# ADC_schematic.net
KiCad netlist of a schematic drawn in Altium Designer
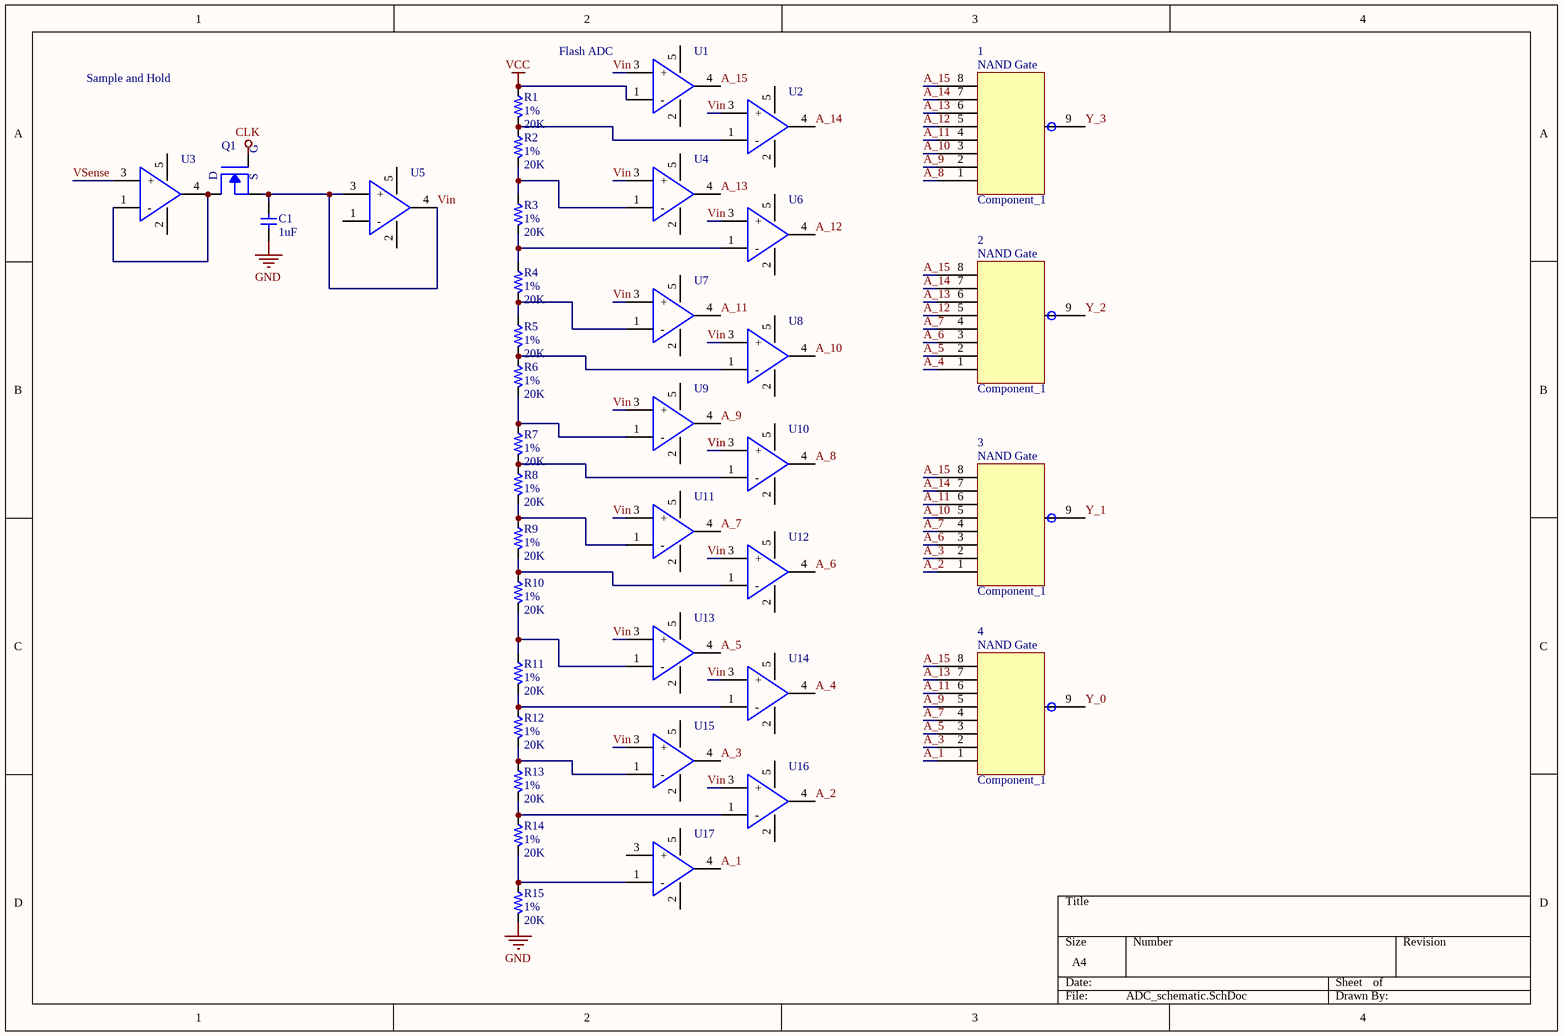
[diagram p0: ADC_schematic.SchDoc]

(export (version "E")
  (design (tool "Eeschema 10.0.6"))
  (components
    (comp (ref "1") (value "Component_1") (libsource (lib "8_in_NAND") (part "Component_1")))
    (comp (ref "2") (value "Component_1") (libsource (lib "8_in_NAND") (part "Component_1")))
    (comp (ref "3") (value "Component_1") (libsource (lib "8_in_NAND") (part "Component_1")))
    (comp (ref "4") (value "Component_1") (libsource (lib "8_in_NAND") (part "Component_1")))
    (comp (ref "C1")
      (value "1uF")
      (footprint "PCB_GENERIC_SMD_0603")
      (description "CAP CER 0603 1uF 16V X5R 20%")
      (fields (field (name "TOLERANCE") "20%") (field (name "VOLTAGE") "16V"))
      (libsource (lib "CAP") (part "C060-0001U-00"))
    )
    (comp (ref "Q1")
      (value "NMOS - SSM3K333R")
      (footprint "NMOS - SSM3K333R - SOTFL95P180X88-3M")
      (description "MOSFET N CH 30V 6A 2-3Z1A")
      (libsource (lib "NMOS") (part "NMOS - SSM3K333R"))
    )
    (comp (ref "R1")
      (value "20K")
      (footprint "PCB_GENERIC_SMD_0603")
      (description "RES 0603 10K 1% 100mW")
      (fields
        (field (name "POWER") "100mW")
        (field (name "TOLERANCE") "1%")
        (field (name "Comment") "R060-00103-01")
      )
      (libsource (lib "RES") (part "R060-00103-01"))
    )
    (comp (ref "R2")
      (value "20K")
      (footprint "PCB_GENERIC_SMD_0603")
      (description "RES 0603 10K 1% 100mW")
      (fields
        (field (name "POWER") "100mW")
        (field (name "TOLERANCE") "1%")
        (field (name "Comment") "R060-00103-01")
      )
      (libsource (lib "RES") (part "R060-00103-01"))
    )
    (comp (ref "R3")
      (value "20K")
      (footprint "PCB_GENERIC_SMD_0603")
      (description "RES 0603 10K 1% 100mW")
      (fields
        (field (name "POWER") "100mW")
        (field (name "TOLERANCE") "1%")
        (field (name "Comment") "R060-00103-01")
      )
      (libsource (lib "RES") (part "R060-00103-01"))
    )
    (comp (ref "R4")
      (value "20K")
      (footprint "PCB_GENERIC_SMD_0603")
      (description "RES 0603 10K 1% 100mW")
      (fields
        (field (name "POWER") "100mW")
        (field (name "TOLERANCE") "1%")
        (field (name "Comment") "R060-00103-01")
      )
      (libsource (lib "RES") (part "R060-00103-01"))
    )
    (comp (ref "R5")
      (value "20K")
      (footprint "PCB_GENERIC_SMD_0603")
      (description "RES 0603 10K 1% 100mW")
      (fields
        (field (name "POWER") "100mW")
        (field (name "TOLERANCE") "1%")
        (field (name "Comment") "R060-00103-01")
      )
      (libsource (lib "RES") (part "R060-00103-01"))
    )
    (comp (ref "R6")
      (value "20K")
      (footprint "PCB_GENERIC_SMD_0603")
      (description "RES 0603 10K 1% 100mW")
      (fields
        (field (name "POWER") "100mW")
        (field (name "TOLERANCE") "1%")
        (field (name "Comment") "R060-00103-01")
      )
      (libsource (lib "RES") (part "R060-00103-01"))
    )
    (comp (ref "R7")
      (value "20K")
      (footprint "PCB_GENERIC_SMD_0603")
      (description "RES 0603 10K 1% 100mW")
      (fields
        (field (name "POWER") "100mW")
        (field (name "TOLERANCE") "1%")
        (field (name "Comment") "R060-00103-01")
      )
      (libsource (lib "RES") (part "R060-00103-01"))
    )
    (comp (ref "R8")
      (value "20K")
      (footprint "PCB_GENERIC_SMD_0603")
      (description "RES 0603 10K 1% 100mW")
      (fields
        (field (name "POWER") "100mW")
        (field (name "TOLERANCE") "1%")
        (field (name "Comment") "R060-00103-01")
      )
      (libsource (lib "RES") (part "R060-00103-01"))
    )
    (comp (ref "R9")
      (value "20K")
      (footprint "PCB_GENERIC_SMD_0603")
      (description "RES 0603 10K 1% 100mW")
      (fields
        (field (name "POWER") "100mW")
        (field (name "TOLERANCE") "1%")
        (field (name "Comment") "R060-00103-01")
      )
      (libsource (lib "RES") (part "R060-00103-01"))
    )
    (comp (ref "R10")
      (value "20K")
      (footprint "PCB_GENERIC_SMD_0603")
      (description "RES 0603 10K 1% 100mW")
      (fields
        (field (name "POWER") "100mW")
        (field (name "TOLERANCE") "1%")
        (field (name "Comment") "R060-00103-01")
      )
      (libsource (lib "RES") (part "R060-00103-01"))
    )
    (comp (ref "R11")
      (value "20K")
      (footprint "PCB_GENERIC_SMD_0603")
      (description "RES 0603 10K 1% 100mW")
      (fields
        (field (name "POWER") "100mW")
        (field (name "TOLERANCE") "1%")
        (field (name "Comment") "R060-00103-01")
      )
      (libsource (lib "RES") (part "R060-00103-01"))
    )
    (comp (ref "R12")
      (value "20K")
      (footprint "PCB_GENERIC_SMD_0603")
      (description "RES 0603 10K 1% 100mW")
      (fields
        (field (name "POWER") "100mW")
        (field (name "TOLERANCE") "1%")
        (field (name "Comment") "R060-00103-01")
      )
      (libsource (lib "RES") (part "R060-00103-01"))
    )
    (comp (ref "R13")
      (value "20K")
      (footprint "PCB_GENERIC_SMD_0603")
      (description "RES 0603 10K 1% 100mW")
      (fields
        (field (name "POWER") "100mW")
        (field (name "TOLERANCE") "1%")
        (field (name "Comment") "R060-00103-01")
      )
      (libsource (lib "RES") (part "R060-00103-01"))
    )
    (comp (ref "R14")
      (value "20K")
      (footprint "PCB_GENERIC_SMD_0603")
      (description "RES 0603 10K 1% 100mW")
      (fields
        (field (name "POWER") "100mW")
        (field (name "TOLERANCE") "1%")
        (field (name "Comment") "R060-00103-01")
      )
      (libsource (lib "RES") (part "R060-00103-01"))
    )
    (comp (ref "R15")
      (value "20K")
      (footprint "PCB_GENERIC_SMD_0603")
      (description "RES 0603 10K 1% 100mW")
      (fields
        (field (name "POWER") "100mW")
        (field (name "TOLERANCE") "1%")
        (field (name "Comment") "R060-00103-01")
      )
      (libsource (lib "RES") (part "R060-00103-01"))
    )
    (comp (ref "U1")
      (value "AP331A")
      (footprint "SOT95P285X130-5N")
      (description "Single Channel Comparator, Open Drain, SC-74A/SOT-753")
      (libsource (lib "Op_Amp") (part "AP331A"))
    )
    (comp (ref "U2")
      (value "AP331A")
      (footprint "SOT95P285X130-5N")
      (description "Single Channel Comparator, Open Drain, SC-74A/SOT-753")
      (libsource (lib "Op_Amp") (part "AP331A"))
    )
    (comp (ref "U3")
      (value "AP331A")
      (footprint "SOT95P285X130-5N")
      (description "Single Channel Comparator, Open Drain, SC-74A/SOT-753")
      (libsource (lib "Op_Amp") (part "AP331A"))
    )
    (comp (ref "U4")
      (value "AP331A")
      (footprint "SOT95P285X130-5N")
      (description "Single Channel Comparator, Open Drain, SC-74A/SOT-753")
      (libsource (lib "Op_Amp") (part "AP331A"))
    )
    (comp (ref "U5")
      (value "AP331A")
      (footprint "SOT95P285X130-5N")
      (description "Single Channel Comparator, Open Drain, SC-74A/SOT-753")
      (libsource (lib "Op_Amp") (part "AP331A"))
    )
    (comp (ref "U6")
      (value "AP331A")
      (footprint "SOT95P285X130-5N")
      (description "Single Channel Comparator, Open Drain, SC-74A/SOT-753")
      (libsource (lib "Op_Amp") (part "AP331A"))
    )
    (comp (ref "U7")
      (value "AP331A")
      (footprint "SOT95P285X130-5N")
      (description "Single Channel Comparator, Open Drain, SC-74A/SOT-753")
      (libsource (lib "Op_Amp") (part "AP331A"))
    )
    (comp (ref "U8")
      (value "AP331A")
      (footprint "SOT95P285X130-5N")
      (description "Single Channel Comparator, Open Drain, SC-74A/SOT-753")
      (libsource (lib "Op_Amp") (part "AP331A"))
    )
    (comp (ref "U9")
      (value "AP331A")
      (footprint "SOT95P285X130-5N")
      (description "Single Channel Comparator, Open Drain, SC-74A/SOT-753")
      (libsource (lib "Op_Amp") (part "AP331A"))
    )
    (comp (ref "U10")
      (value "AP331A")
      (footprint "SOT95P285X130-5N")
      (description "Single Channel Comparator, Open Drain, SC-74A/SOT-753")
      (libsource (lib "Op_Amp") (part "AP331A"))
    )
    (comp (ref "U11")
      (value "AP331A")
      (footprint "SOT95P285X130-5N")
      (description "Single Channel Comparator, Open Drain, SC-74A/SOT-753")
      (libsource (lib "Op_Amp") (part "AP331A"))
    )
    (comp (ref "U12")
      (value "AP331A")
      (footprint "SOT95P285X130-5N")
      (description "Single Channel Comparator, Open Drain, SC-74A/SOT-753")
      (libsource (lib "Op_Amp") (part "AP331A"))
    )
    (comp (ref "U13")
      (value "AP331A")
      (footprint "SOT95P285X130-5N")
      (description "Single Channel Comparator, Open Drain, SC-74A/SOT-753")
      (libsource (lib "Op_Amp") (part "AP331A"))
    )
    (comp (ref "U14")
      (value "AP331A")
      (footprint "SOT95P285X130-5N")
      (description "Single Channel Comparator, Open Drain, SC-74A/SOT-753")
      (libsource (lib "Op_Amp") (part "AP331A"))
    )
    (comp (ref "U15")
      (value "AP331A")
      (footprint "SOT95P285X130-5N")
      (description "Single Channel Comparator, Open Drain, SC-74A/SOT-753")
      (libsource (lib "Op_Amp") (part "AP331A"))
    )
    (comp (ref "U16")
      (value "AP331A")
      (footprint "SOT95P285X130-5N")
      (description "Single Channel Comparator, Open Drain, SC-74A/SOT-753")
      (libsource (lib "Op_Amp") (part "AP331A"))
    )
    (comp (ref "U17")
      (value "AP331A")
      (footprint "SOT95P285X130-5N")
      (description "Single Channel Comparator, Open Drain, SC-74A/SOT-753")
      (libsource (lib "Op_Amp") (part "AP331A"))
    )
  )
  (nets
    (net (code "1") (name "/A_1") (class "Default")
      (node (ref "4") (pin "1") (pinfunction "1_1") (pintype "passive"))
      (node (ref "U17") (pin "4") (pinfunction "VOUT_4") (pintype "passive"))
    )
    (net (code "2") (name "/A_2") (class "Default")
      (node (ref "3") (pin "1") (pinfunction "1_1") (pintype "passive"))
      (node (ref "U16") (pin "4") (pinfunction "VOUT_4") (pintype "passive"))
    )
    (net (code "3") (name "/A_3") (class "Default")
      (node (ref "3") (pin "2") (pinfunction "2_2") (pintype "passive"))
      (node (ref "4") (pin "2") (pinfunction "2_2") (pintype "passive"))
      (node (ref "U15") (pin "4") (pinfunction "VOUT_4") (pintype "passive"))
    )
    (net (code "4") (name "/A_4") (class "Default")
      (node (ref "2") (pin "1") (pinfunction "1_1") (pintype "passive"))
      (node (ref "U14") (pin "4") (pinfunction "VOUT_4") (pintype "passive"))
    )
    (net (code "5") (name "/A_5") (class "Default")
      (node (ref "2") (pin "2") (pinfunction "2_2") (pintype "passive"))
      (node (ref "4") (pin "3") (pinfunction "3_3") (pintype "passive"))
      (node (ref "U13") (pin "4") (pinfunction "VOUT_4") (pintype "passive"))
    )
    (net (code "6") (name "/A_6") (class "Default")
      (node (ref "2") (pin "3") (pinfunction "3_3") (pintype "passive"))
      (node (ref "3") (pin "3") (pinfunction "3_3") (pintype "passive"))
      (node (ref "U12") (pin "4") (pinfunction "VOUT_4") (pintype "passive"))
    )
    (net (code "7") (name "/A_7") (class "Default")
      (node (ref "2") (pin "4") (pinfunction "4_4") (pintype "passive"))
      (node (ref "3") (pin "4") (pinfunction "4_4") (pintype "passive"))
      (node (ref "4") (pin "4") (pinfunction "4_4") (pintype "passive"))
      (node (ref "U11") (pin "4") (pinfunction "VOUT_4") (pintype "passive"))
    )
    (net (code "8") (name "/A_8") (class "Default")
      (node (ref "1") (pin "1") (pinfunction "1_1") (pintype "passive"))
      (node (ref "U10") (pin "4") (pinfunction "VOUT_4") (pintype "passive"))
    )
    (net (code "9") (name "/A_9") (class "Default")
      (node (ref "1") (pin "2") (pinfunction "2_2") (pintype "passive"))
      (node (ref "4") (pin "5") (pinfunction "5_5") (pintype "passive"))
      (node (ref "U9") (pin "4") (pinfunction "VOUT_4") (pintype "passive"))
    )
    (net (code "10") (name "/A_10") (class "Default")
      (node (ref "1") (pin "3") (pinfunction "3_3") (pintype "passive"))
      (node (ref "3") (pin "5") (pinfunction "5_5") (pintype "passive"))
      (node (ref "U8") (pin "4") (pinfunction "VOUT_4") (pintype "passive"))
    )
    (net (code "11") (name "/A_11") (class "Default")
      (node (ref "1") (pin "4") (pinfunction "4_4") (pintype "passive"))
      (node (ref "3") (pin "6") (pinfunction "6_6") (pintype "passive"))
      (node (ref "4") (pin "6") (pinfunction "6_6") (pintype "passive"))
      (node (ref "U7") (pin "4") (pinfunction "VOUT_4") (pintype "passive"))
    )
    (net (code "12") (name "/A_12") (class "Default")
      (node (ref "1") (pin "5") (pinfunction "5_5") (pintype "passive"))
      (node (ref "2") (pin "5") (pinfunction "5_5") (pintype "passive"))
      (node (ref "U6") (pin "4") (pinfunction "VOUT_4") (pintype "passive"))
    )
    (net (code "13") (name "/A_13") (class "Default")
      (node (ref "1") (pin "6") (pinfunction "6_6") (pintype "passive"))
      (node (ref "2") (pin "6") (pinfunction "6_6") (pintype "passive"))
      (node (ref "4") (pin "7") (pinfunction "7_7") (pintype "passive"))
      (node (ref "U4") (pin "4") (pinfunction "VOUT_4") (pintype "passive"))
    )
    (net (code "14") (name "/A_14") (class "Default")
      (node (ref "1") (pin "7") (pinfunction "7_7") (pintype "passive"))
      (node (ref "2") (pin "7") (pinfunction "7_7") (pintype "passive"))
      (node (ref "3") (pin "7") (pinfunction "7_7") (pintype "passive"))
      (node (ref "U2") (pin "4") (pinfunction "VOUT_4") (pintype "passive"))
    )
    (net (code "15") (name "/A_15") (class "Default")
      (node (ref "1") (pin "8") (pinfunction "8_8") (pintype "passive"))
      (node (ref "2") (pin "8") (pinfunction "8_8") (pintype "passive"))
      (node (ref "3") (pin "8") (pinfunction "8_8") (pintype "passive"))
      (node (ref "4") (pin "8") (pinfunction "8_8") (pintype "passive"))
      (node (ref "U1") (pin "4") (pinfunction "VOUT_4") (pintype "passive"))
    )
    (net (code "16") (name "/VSense") (class "Default")
      (node (ref "U3") (pin "3") (pinfunction "+_3") (pintype "passive"))
    )
    (net (code "17") (name "/Vin") (class "Default")
      (node (ref "C1") (pin "2") (pinfunction "2_2") (pintype "passive"))
      (node (ref "Q1") (pin "2") (pinfunction "S_2") (pintype "passive"))
      (node (ref "U1") (pin "3") (pinfunction "+_3") (pintype "passive"))
      (node (ref "U10") (pin "3") (pinfunction "+_3") (pintype "passive"))
      (node (ref "U11") (pin "3") (pinfunction "+_3") (pintype "passive"))
      (node (ref "U12") (pin "3") (pinfunction "+_3") (pintype "passive"))
      (node (ref "U13") (pin "3") (pinfunction "+_3") (pintype "passive"))
      (node (ref "U14") (pin "3") (pinfunction "+_3") (pintype "passive"))
      (node (ref "U15") (pin "3") (pinfunction "+_3") (pintype "passive"))
      (node (ref "U16") (pin "3") (pinfunction "+_3") (pintype "passive"))
      (node (ref "U2") (pin "3") (pinfunction "+_3") (pintype "passive"))
      (node (ref "U4") (pin "3") (pinfunction "+_3") (pintype "passive"))
      (node (ref "U5") (pin "3") (pinfunction "+_3") (pintype "passive"))
      (node (ref "U5") (pin "4") (pinfunction "VOUT_4") (pintype "passive"))
      (node (ref "U6") (pin "3") (pinfunction "+_3") (pintype "passive"))
      (node (ref "U7") (pin "3") (pinfunction "+_3") (pintype "passive"))
      (node (ref "U8") (pin "3") (pinfunction "+_3") (pintype "passive"))
      (node (ref "U9") (pin "3") (pinfunction "+_3") (pintype "passive"))
    )
    (net (code "22") (name "CLK") (class "Default")
      (node (ref "Q1") (pin "1") (pinfunction "G_1") (pintype "passive"))
    )
    (net (code "23") (name "GND") (class "Default")
      (node (ref "C1") (pin "1") (pinfunction "1_1") (pintype "passive"))
      (node (ref "R15") (pin "2") (pinfunction "2_2") (pintype "passive"))
    )
    (net (code "24") (name "Net-(Q1-D)") (class "Default")
      (node (ref "Q1") (pin "3") (pinfunction "D_3") (pintype "passive"))
      (node (ref "U3") (pin "1") (pinfunction "-_1") (pintype "passive"))
      (node (ref "U3") (pin "4") (pinfunction "VOUT_4") (pintype "passive"))
    )
    (net (code "25") (name "Net-(U2--)") (class "Default")
      (node (ref "R1") (pin "2") (pinfunction "2_2") (pintype "passive"))
      (node (ref "R2") (pin "1") (pinfunction "1_1") (pintype "passive"))
      (node (ref "U2") (pin "1") (pinfunction "-_1") (pintype "passive"))
    )
    (net (code "26") (name "Net-(U4--)") (class "Default")
      (node (ref "R2") (pin "2") (pinfunction "2_2") (pintype "passive"))
      (node (ref "R3") (pin "1") (pinfunction "1_1") (pintype "passive"))
      (node (ref "U4") (pin "1") (pinfunction "-_1") (pintype "passive"))
    )
    (net (code "27") (name "Net-(U6--)") (class "Default")
      (node (ref "R3") (pin "2") (pinfunction "2_2") (pintype "passive"))
      (node (ref "R4") (pin "1") (pinfunction "1_1") (pintype "passive"))
      (node (ref "U6") (pin "1") (pinfunction "-_1") (pintype "passive"))
    )
    (net (code "28") (name "Net-(U7--)") (class "Default")
      (node (ref "R4") (pin "2") (pinfunction "2_2") (pintype "passive"))
      (node (ref "R5") (pin "1") (pinfunction "1_1") (pintype "passive"))
      (node (ref "U7") (pin "1") (pinfunction "-_1") (pintype "passive"))
    )
    (net (code "29") (name "Net-(U8--)") (class "Default")
      (node (ref "R5") (pin "2") (pinfunction "2_2") (pintype "passive"))
      (node (ref "R6") (pin "1") (pinfunction "1_1") (pintype "passive"))
      (node (ref "U8") (pin "1") (pinfunction "-_1") (pintype "passive"))
    )
    (net (code "30") (name "Net-(U9--)") (class "Default")
      (node (ref "R6") (pin "2") (pinfunction "2_2") (pintype "passive"))
      (node (ref "R7") (pin "1") (pinfunction "1_1") (pintype "passive"))
      (node (ref "U9") (pin "1") (pinfunction "-_1") (pintype "passive"))
    )
    (net (code "31") (name "Net-(U10--)") (class "Default")
      (node (ref "R7") (pin "2") (pinfunction "2_2") (pintype "passive"))
      (node (ref "R8") (pin "1") (pinfunction "1_1") (pintype "passive"))
      (node (ref "U10") (pin "1") (pinfunction "-_1") (pintype "passive"))
    )
    (net (code "32") (name "Net-(U11--)") (class "Default")
      (node (ref "R8") (pin "2") (pinfunction "2_2") (pintype "passive"))
      (node (ref "R9") (pin "1") (pinfunction "1_1") (pintype "passive"))
      (node (ref "U11") (pin "1") (pinfunction "-_1") (pintype "passive"))
    )
    (net (code "33") (name "Net-(U12--)") (class "Default")
      (node (ref "R10") (pin "1") (pinfunction "1_1") (pintype "passive"))
      (node (ref "R9") (pin "2") (pinfunction "2_2") (pintype "passive"))
      (node (ref "U12") (pin "1") (pinfunction "-_1") (pintype "passive"))
    )
    (net (code "34") (name "Net-(U13--)") (class "Default")
      (node (ref "R10") (pin "2") (pinfunction "2_2") (pintype "passive"))
      (node (ref "R11") (pin "1") (pinfunction "1_1") (pintype "passive"))
      (node (ref "U13") (pin "1") (pinfunction "-_1") (pintype "passive"))
    )
    (net (code "35") (name "Net-(U14--)") (class "Default")
      (node (ref "R11") (pin "2") (pinfunction "2_2") (pintype "passive"))
      (node (ref "R12") (pin "1") (pinfunction "1_1") (pintype "passive"))
      (node (ref "U14") (pin "1") (pinfunction "-_1") (pintype "passive"))
    )
    (net (code "36") (name "Net-(U15--)") (class "Default")
      (node (ref "R12") (pin "2") (pinfunction "2_2") (pintype "passive"))
      (node (ref "R13") (pin "1") (pinfunction "1_1") (pintype "passive"))
      (node (ref "U15") (pin "1") (pinfunction "-_1") (pintype "passive"))
    )
    (net (code "37") (name "Net-(U16--)") (class "Default")
      (node (ref "R13") (pin "2") (pinfunction "2_2") (pintype "passive"))
      (node (ref "R14") (pin "1") (pinfunction "1_1") (pintype "passive"))
      (node (ref "U16") (pin "1") (pinfunction "-_1") (pintype "passive"))
    )
    (net (code "38") (name "Net-(U17--)") (class "Default")
      (node (ref "R14") (pin "2") (pinfunction "2_2") (pintype "passive"))
      (node (ref "R15") (pin "1") (pinfunction "1_1") (pintype "passive"))
      (node (ref "U17") (pin "1") (pinfunction "-_1") (pintype "passive"))
    )
    (net (code "39") (name "VCC") (class "Default")
      (node (ref "R1") (pin "1") (pinfunction "1_1") (pintype "passive"))
      (node (ref "U1") (pin "1") (pinfunction "-_1") (pintype "passive"))
    )
    (net (code "40") (name "unconnected-(1-Pad9)") (class "Default")
      (node (ref "1") (pin "9") (pinfunction "9_9") (pintype "passive"))
    )
    (net (code "41") (name "unconnected-(2-Pad9)") (class "Default")
      (node (ref "2") (pin "9") (pinfunction "9_9") (pintype "passive"))
    )
    (net (code "42") (name "unconnected-(3-Pad9)") (class "Default")
      (node (ref "3") (pin "9") (pinfunction "9_9") (pintype "passive"))
    )
    (net (code "43") (name "unconnected-(4-Pad9)") (class "Default")
      (node (ref "4") (pin "9") (pinfunction "9_9") (pintype "passive"))
    )
    (net (code "44") (name "unconnected-(U1-GND-Pad2)") (class "Default")
      (node (ref "U1") (pin "2") (pinfunction "GND_2") (pintype "passive"))
    )
    (net (code "45") (name "unconnected-(U1-VCC-Pad5)") (class "Default")
      (node (ref "U1") (pin "5") (pinfunction "VCC_5") (pintype "passive"))
    )
    (net (code "46") (name "unconnected-(U2-GND-Pad2)") (class "Default")
      (node (ref "U2") (pin "2") (pinfunction "GND_2") (pintype "passive"))
    )
    (net (code "47") (name "unconnected-(U2-VCC-Pad5)") (class "Default")
      (node (ref "U2") (pin "5") (pinfunction "VCC_5") (pintype "passive"))
    )
    (net (code "48") (name "unconnected-(U3-GND-Pad2)") (class "Default")
      (node (ref "U3") (pin "2") (pinfunction "GND_2") (pintype "passive"))
    )
    (net (code "49") (name "unconnected-(U3-VCC-Pad5)") (class "Default")
      (node (ref "U3") (pin "5") (pinfunction "VCC_5") (pintype "passive"))
    )
    (net (code "50") (name "unconnected-(U4-GND-Pad2)") (class "Default")
      (node (ref "U4") (pin "2") (pinfunction "GND_2") (pintype "passive"))
    )
    (net (code "51") (name "unconnected-(U4-VCC-Pad5)") (class "Default")
      (node (ref "U4") (pin "5") (pinfunction "VCC_5") (pintype "passive"))
    )
    (net (code "52") (name "unconnected-(U5---Pad1)") (class "Default")
      (node (ref "U5") (pin "1") (pinfunction "-_1") (pintype "passive"))
    )
    (net (code "53") (name "unconnected-(U5-GND-Pad2)") (class "Default")
      (node (ref "U5") (pin "2") (pinfunction "GND_2") (pintype "passive"))
    )
    (net (code "54") (name "unconnected-(U5-VCC-Pad5)") (class "Default")
      (node (ref "U5") (pin "5") (pinfunction "VCC_5") (pintype "passive"))
    )
    (net (code "55") (name "unconnected-(U6-GND-Pad2)") (class "Default")
      (node (ref "U6") (pin "2") (pinfunction "GND_2") (pintype "passive"))
    )
    (net (code "56") (name "unconnected-(U6-VCC-Pad5)") (class "Default")
      (node (ref "U6") (pin "5") (pinfunction "VCC_5") (pintype "passive"))
    )
    (net (code "57") (name "unconnected-(U7-GND-Pad2)") (class "Default")
      (node (ref "U7") (pin "2") (pinfunction "GND_2") (pintype "passive"))
    )
    (net (code "58") (name "unconnected-(U7-VCC-Pad5)") (class "Default")
      (node (ref "U7") (pin "5") (pinfunction "VCC_5") (pintype "passive"))
    )
    (net (code "59") (name "unconnected-(U8-GND-Pad2)") (class "Default")
      (node (ref "U8") (pin "2") (pinfunction "GND_2") (pintype "passive"))
    )
    (net (code "60") (name "unconnected-(U8-VCC-Pad5)") (class "Default")
      (node (ref "U8") (pin "5") (pinfunction "VCC_5") (pintype "passive"))
    )
    (net (code "61") (name "unconnected-(U9-GND-Pad2)") (class "Default")
      (node (ref "U9") (pin "2") (pinfunction "GND_2") (pintype "passive"))
    )
    (net (code "62") (name "unconnected-(U9-VCC-Pad5)") (class "Default")
      (node (ref "U9") (pin "5") (pinfunction "VCC_5") (pintype "passive"))
    )
    (net (code "63") (name "unconnected-(U10-GND-Pad2)") (class "Default")
      (node (ref "U10") (pin "2") (pinfunction "GND_2") (pintype "passive"))
    )
    (net (code "64") (name "unconnected-(U10-VCC-Pad5)") (class "Default")
      (node (ref "U10") (pin "5") (pinfunction "VCC_5") (pintype "passive"))
    )
    (net (code "65") (name "unconnected-(U11-GND-Pad2)") (class "Default")
      (node (ref "U11") (pin "2") (pinfunction "GND_2") (pintype "passive"))
    )
    (net (code "66") (name "unconnected-(U11-VCC-Pad5)") (class "Default")
      (node (ref "U11") (pin "5") (pinfunction "VCC_5") (pintype "passive"))
    )
    (net (code "67") (name "unconnected-(U12-GND-Pad2)") (class "Default")
      (node (ref "U12") (pin "2") (pinfunction "GND_2") (pintype "passive"))
    )
    (net (code "68") (name "unconnected-(U12-VCC-Pad5)") (class "Default")
      (node (ref "U12") (pin "5") (pinfunction "VCC_5") (pintype "passive"))
    )
    (net (code "69") (name "unconnected-(U13-GND-Pad2)") (class "Default")
      (node (ref "U13") (pin "2") (pinfunction "GND_2") (pintype "passive"))
    )
    (net (code "70") (name "unconnected-(U13-VCC-Pad5)") (class "Default")
      (node (ref "U13") (pin "5") (pinfunction "VCC_5") (pintype "passive"))
    )
    (net (code "71") (name "unconnected-(U14-GND-Pad2)") (class "Default")
      (node (ref "U14") (pin "2") (pinfunction "GND_2") (pintype "passive"))
    )
    (net (code "72") (name "unconnected-(U14-VCC-Pad5)") (class "Default")
      (node (ref "U14") (pin "5") (pinfunction "VCC_5") (pintype "passive"))
    )
    (net (code "73") (name "unconnected-(U15-GND-Pad2)") (class "Default")
      (node (ref "U15") (pin "2") (pinfunction "GND_2") (pintype "passive"))
    )
    (net (code "74") (name "unconnected-(U15-VCC-Pad5)") (class "Default")
      (node (ref "U15") (pin "5") (pinfunction "VCC_5") (pintype "passive"))
    )
    (net (code "75") (name "unconnected-(U16-GND-Pad2)") (class "Default")
      (node (ref "U16") (pin "2") (pinfunction "GND_2") (pintype "passive"))
    )
    (net (code "76") (name "unconnected-(U16-VCC-Pad5)") (class "Default")
      (node (ref "U16") (pin "5") (pinfunction "VCC_5") (pintype "passive"))
    )
    (net (code "77") (name "unconnected-(U17-+-Pad3)") (class "Default")
      (node (ref "U17") (pin "3") (pinfunction "+_3") (pintype "passive"))
    )
    (net (code "78") (name "unconnected-(U17-GND-Pad2)") (class "Default")
      (node (ref "U17") (pin "2") (pinfunction "GND_2") (pintype "passive"))
    )
    (net (code "79") (name "unconnected-(U17-VCC-Pad5)") (class "Default")
      (node (ref "U17") (pin "5") (pinfunction "VCC_5") (pintype "passive"))
    )
  )
)
